# 20190105_ORIGAMI_V1-H.net
KiCad netlist of a schematic drawn in EAGLE
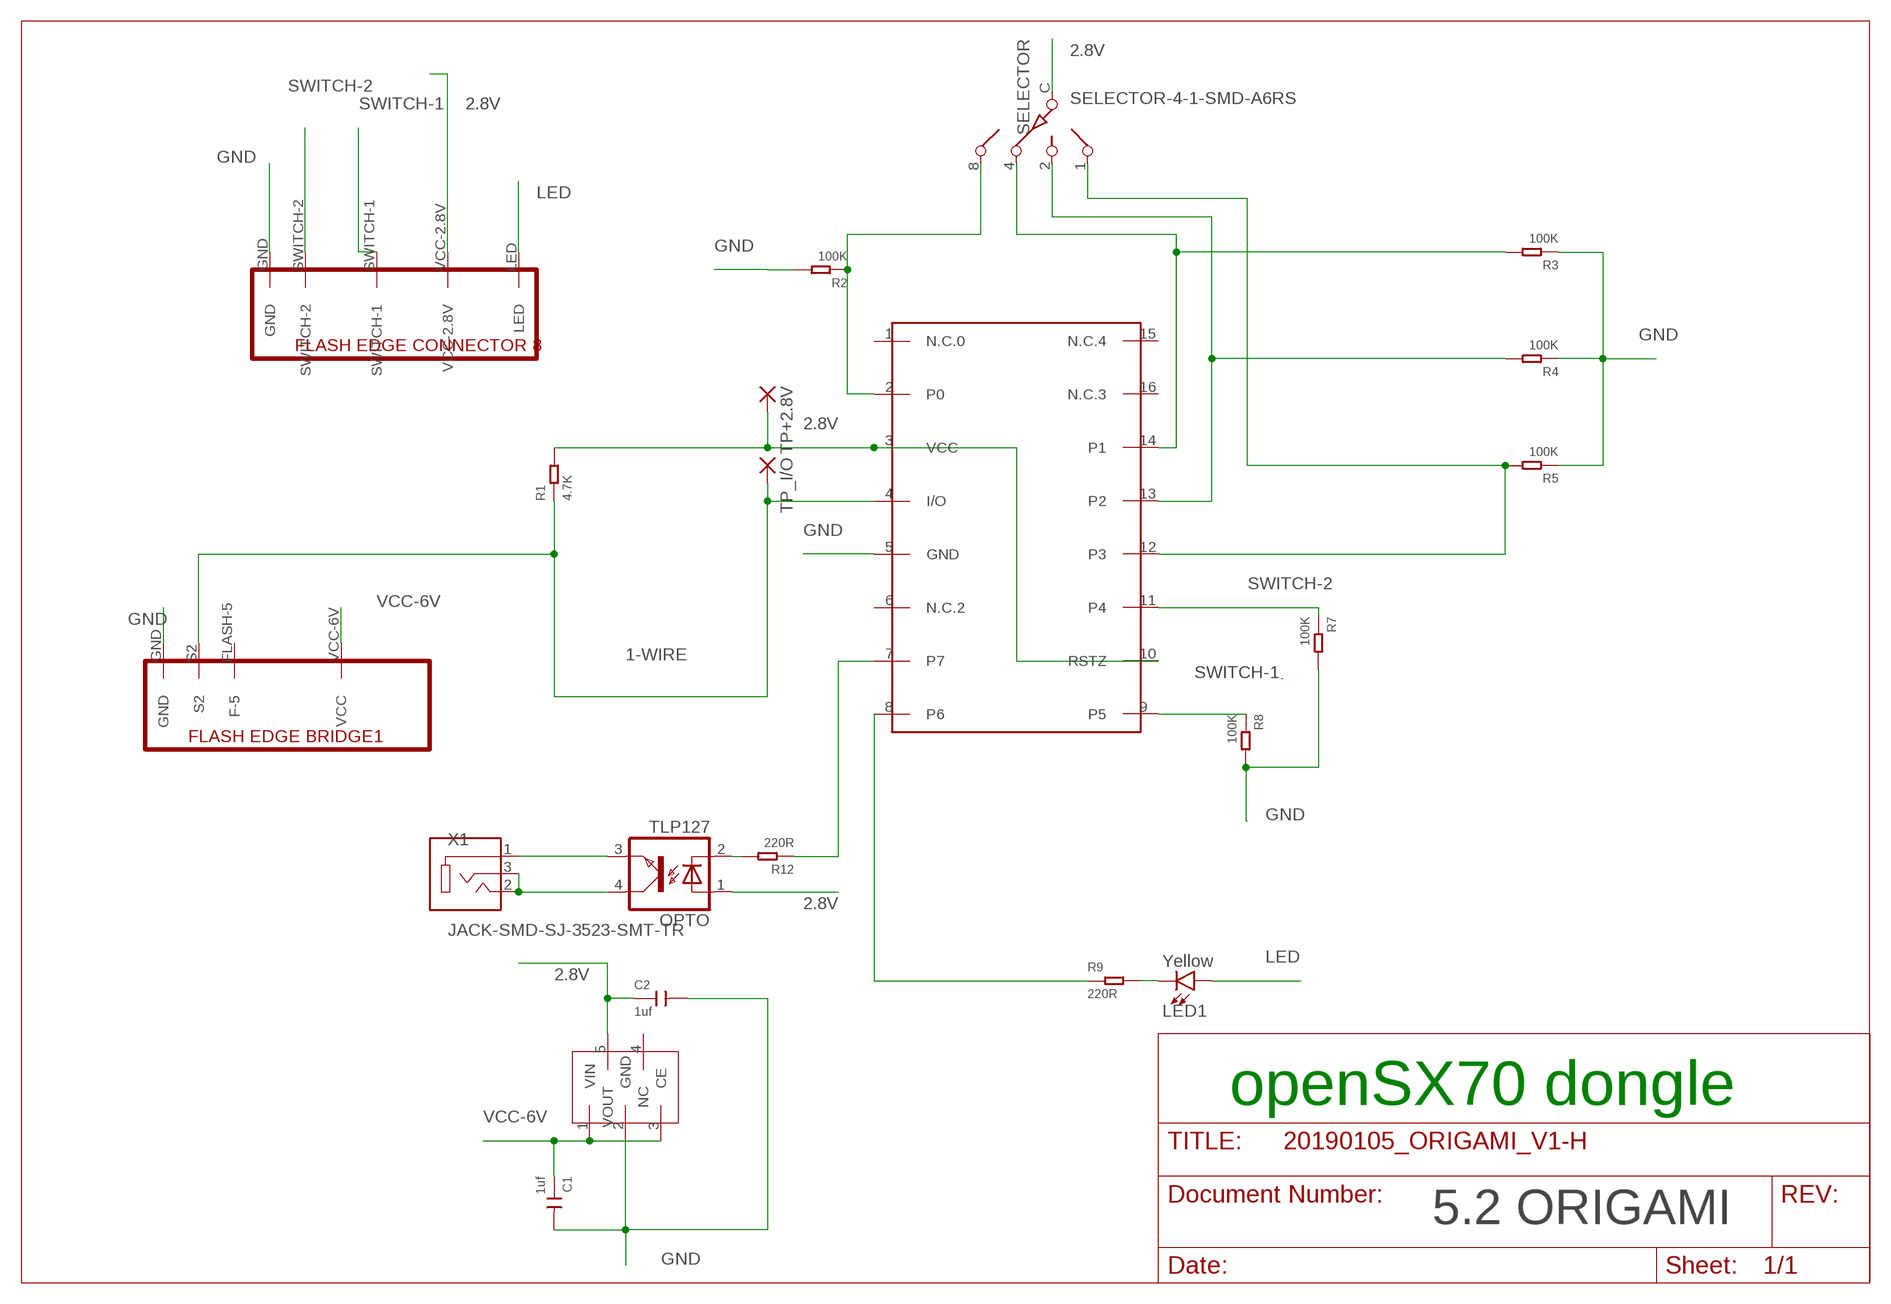
[diagram p0: schematic, sheet 1]

(export (version "E")
  (design (tool "Eeschema 10.0.6"))
  (components
    (comp (ref "C1")
      (value "1uf")
      (footprint "eagle-import:C0603")
      (fields (field (name "MPN") "CC0603KRX7R8BB105"))
      (libsource (lib "eagle-import") (part "CERAMIC-1UF-25V-10%-X7R(0603)"))
    )
    (comp (ref "C2")
      (value "1uf")
      (footprint "eagle-import:C0603")
      (fields (field (name "MPN") "CC0603KRX7R8BB105"))
      (libsource (lib "eagle-import") (part "CERAMIC-1UF-25V-10%-X7R(0603)"))
    )
    (comp (ref "DS2408")
      (value "DS2408")
      (footprint "eagle-import:SO16")
      (libsource (lib "eagle-import") (part "DS2408"))
    )
    (comp (ref "LED1")
      (value "Yellow")
      (footprint "eagle-import:LED-1206")
      (libsource (lib "eagle-import") (part "LED-YELLOWLILYPAD"))
    )
    (comp (ref "OPTO")
      (value "TLP127")
      (footprint "eagle-import:SO-4")
      (libsource (lib "eagle-import") (part "TLP127"))
    )
    (comp (ref "R1")
      (value "4.7K")
      (footprint "eagle-import:R0603")
      (fields (field (name "MPN") "RC0603JR-074K7L"))
      (libsource (lib "eagle-import") (part "SMD-RES-4.7K-5%-1/10W(0603)"))
    )
    (comp (ref "R2")
      (value "100K")
      (footprint "eagle-import:R0603")
      (fields (field (name "MPN") "RC0603FR-07100KL"))
      (libsource (lib "eagle-import") (part "SMD-RES-100K-1%-1/10W(0603)"))
    )
    (comp (ref "R3")
      (value "100K")
      (footprint "eagle-import:R0603")
      (fields (field (name "MPN") "RC0603FR-07100KL"))
      (libsource (lib "eagle-import") (part "SMD-RES-100K-1%-1/10W(0603)"))
    )
    (comp (ref "R4")
      (value "100K")
      (footprint "eagle-import:R0603")
      (fields (field (name "MPN") "RC0603FR-07100KL"))
      (libsource (lib "eagle-import") (part "SMD-RES-100K-1%-1/10W(0603)"))
    )
    (comp (ref "R5")
      (value "100K")
      (footprint "eagle-import:R0603")
      (fields (field (name "MPN") "RC0603FR-07100KL"))
      (libsource (lib "eagle-import") (part "SMD-RES-100K-1%-1/10W(0603)"))
    )
    (comp (ref "R7")
      (value "100K")
      (footprint "eagle-import:R0603")
      (fields (field (name "MPN") "RC0603FR-07100KL"))
      (libsource (lib "eagle-import") (part "SMD-RES-100K-1%-1/10W(0603)"))
    )
    (comp (ref "R8")
      (value "100K")
      (footprint "eagle-import:R0603")
      (fields (field (name "MPN") "RC0603FR-07100KL"))
      (libsource (lib "eagle-import") (part "SMD-RES-100K-1%-1/10W(0603)"))
    )
    (comp (ref "R9")
      (value "220R")
      (footprint "eagle-import:R0603")
      (fields (field (name "MPN") "RC0603JR-07220RL"))
      (libsource (lib "eagle-import") (part "SMD-RES-220R-5%-1/10W(0603)"))
    )
    (comp (ref "R12")
      (value "220R")
      (footprint "eagle-import:R0603")
      (fields (field (name "MPN") "RC0603JR-07220RL"))
      (libsource (lib "eagle-import") (part "SMD-RES-220R-5%-1/10W(0603)"))
    )
    (comp (ref "REG")
      (value "NCP4688")
      (footprint "eagle-import:SOT-23-5")
      (libsource (lib "eagle-import") (part "NCP4688"))
    )
    (comp (ref "SELECTOR")
      (value "SELECTOR-4-1-SMD-A6RS")
      (footprint "eagle-import:A6RS-161RS")
      (libsource (lib "eagle-import") (part "SELECTOR-4-1-SMD-A6RS"))
    )
    (comp (ref "TP+2.8V")
      (value "SMD2")
      (footprint "eagle-import:SMD1,27-2,54")
      (libsource (lib "eagle-import") (part "SMD2"))
    )
    (comp (ref "TP_I/O")
      (value "SMD2")
      (footprint "eagle-import:SMD1,27-2,54")
      (libsource (lib "eagle-import") (part "SMD2"))
    )
    (comp (ref "U$1")
      (value "FLASH-BRIDGE-SW1-SW2-LED")
      (footprint "eagle-import:FLASH-8-BRIDGE-SW1-SW2-LED")
      (libsource (lib "eagle-import") (part "FLASH-BRIDGE-SW1-SW2-LED"))
    )
    (comp (ref "U$2")
      (value "FLASH-BRIDGE1")
      (footprint "eagle-import:FLASH-8-BRIDGE1")
      (libsource (lib "eagle-import") (part "FLASH-BRIDGE1"))
    )
    (comp (ref "X1")
      (value "JACK-SMD-SJ-3523-SMT-TR")
      (footprint "eagle-import:CUI_SJ-3523-SMT-TR")
      (fields (field (name "MF") "CUI Inc.") (field (name "MP") "SJ-3523-SMT-TR"))
      (libsource (lib "eagle-import") (part "JACK-SMD-SJ-3523-SMT-TR"))
    )
  )
  (nets
    (net (code "1") (name "/1-WIRE") (class "Default")
      (node (ref "DS2408") (pin "4") (pinfunction "I/O_4") (pintype "bidirectional"))
      (node (ref "R1") (pin "1") (pinfunction "1_1") (pintype "passive"))
      (node (ref "TP_I/O") (pin "1") (pinfunction "P_1") (pintype "passive"))
      (node (ref "U$2") (pin "S2") (pinfunction "S2_S2") (pintype "bidirectional"))
    )
    (net (code "2") (name "/2.8V") (class "Default")
      (node (ref "C2") (pin "1") (pinfunction "1_1") (pintype "passive"))
      (node (ref "DS2408") (pin "10") (pinfunction "RSTZ_10") (pintype "bidirectional"))
      (node (ref "DS2408") (pin "3") (pinfunction "VCC_3") (pintype "bidirectional"))
      (node (ref "OPTO") (pin "1") (pinfunction "A_1") (pintype "passive"))
      (node (ref "R1") (pin "2") (pinfunction "2_2") (pintype "passive"))
      (node (ref "REG") (pin "5") (pinfunction "VOUT_5") (pintype "bidirectional"))
      (node (ref "SELECTOR") (pin "C") (pinfunction "C_C") (pintype "passive"))
      (node (ref "TP+2.8V") (pin "1") (pinfunction "P_1") (pintype "passive"))
      (node (ref "U$1") (pin "VCC-2.8V") (pinfunction "VCC-2.8V_VCC-2.8V") (pintype "bidirectional"))
    )
    (net (code "3") (name "/GND") (class "Default")
      (node (ref "C1") (pin "2") (pinfunction "2_2") (pintype "passive"))
      (node (ref "C2") (pin "2") (pinfunction "2_2") (pintype "passive"))
      (node (ref "DS2408") (pin "5") (pinfunction "GND_5") (pintype "bidirectional"))
      (node (ref "R2") (pin "2") (pinfunction "2_2") (pintype "passive"))
      (node (ref "R3") (pin "1") (pinfunction "1_1") (pintype "passive"))
      (node (ref "R4") (pin "1") (pinfunction "1_1") (pintype "passive"))
      (node (ref "R5") (pin "1") (pinfunction "1_1") (pintype "passive"))
      (node (ref "R7") (pin "2") (pinfunction "2_2") (pintype "passive"))
      (node (ref "R8") (pin "2") (pinfunction "2_2") (pintype "passive"))
      (node (ref "REG") (pin "2") (pinfunction "GND_2") (pintype "bidirectional"))
      (node (ref "U$1") (pin "GND") (pinfunction "GND_GND") (pintype "bidirectional"))
      (node (ref "U$2") (pin "GND") (pinfunction "GND_GND") (pintype "bidirectional"))
    )
    (net (code "4") (name "/LED") (class "Default")
      (node (ref "LED1") (pin "A") (pinfunction "A_A") (pintype "passive"))
      (node (ref "U$1") (pin "LED") (pinfunction "LED_LED") (pintype "bidirectional"))
    )
    (net (code "5") (name "/SWITCH-1") (class "Default")
      (node (ref "DS2408") (pin "9") (pinfunction "P5_9") (pintype "bidirectional"))
      (node (ref "R8") (pin "1") (pinfunction "1_1") (pintype "passive"))
      (node (ref "U$1") (pin "SWITCH-1") (pinfunction "SWITCH-1_SWITCH-1") (pintype "bidirectional"))
    )
    (net (code "6") (name "/SWITCH-2") (class "Default")
      (node (ref "DS2408") (pin "11") (pinfunction "P4_11") (pintype "bidirectional"))
      (node (ref "R7") (pin "1") (pinfunction "1_1") (pintype "passive"))
      (node (ref "U$1") (pin "SWITCH-2") (pinfunction "SWITCH-2_SWITCH-2") (pintype "bidirectional"))
    )
    (net (code "7") (name "/VCC-6V") (class "Default")
      (node (ref "C1") (pin "1") (pinfunction "1_1") (pintype "passive"))
      (node (ref "REG") (pin "1") (pinfunction "VIN_1") (pintype "bidirectional"))
      (node (ref "REG") (pin "3") (pinfunction "CE_3") (pintype "bidirectional"))
      (node (ref "U$2") (pin "VCC-6V") (pinfunction "VCC_VCC-6V") (pintype "bidirectional"))
    )
    (net (code "8") (name "Net-(DS2408-P0)") (class "Default")
      (node (ref "DS2408") (pin "2") (pinfunction "P0_2") (pintype "bidirectional"))
      (node (ref "R2") (pin "1") (pinfunction "1_1") (pintype "passive"))
      (node (ref "SELECTOR") (pin "8") (pinfunction "8_8") (pintype "passive"))
    )
    (net (code "9") (name "Net-(DS2408-P1)") (class "Default")
      (node (ref "DS2408") (pin "14") (pinfunction "P1_14") (pintype "bidirectional"))
      (node (ref "R3") (pin "2") (pinfunction "2_2") (pintype "passive"))
      (node (ref "SELECTOR") (pin "4") (pinfunction "4_4") (pintype "passive"))
    )
    (net (code "10") (name "Net-(DS2408-P2)") (class "Default")
      (node (ref "DS2408") (pin "13") (pinfunction "P2_13") (pintype "bidirectional"))
      (node (ref "R4") (pin "2") (pinfunction "2_2") (pintype "passive"))
      (node (ref "SELECTOR") (pin "2") (pinfunction "2_2") (pintype "passive"))
    )
    (net (code "11") (name "Net-(DS2408-P3)") (class "Default")
      (node (ref "DS2408") (pin "12") (pinfunction "P3_12") (pintype "bidirectional"))
      (node (ref "R5") (pin "2") (pinfunction "2_2") (pintype "passive"))
      (node (ref "SELECTOR") (pin "1") (pinfunction "1_1") (pintype "passive"))
    )
    (net (code "12") (name "Net-(DS2408-P6)") (class "Default")
      (node (ref "DS2408") (pin "8") (pinfunction "P6_8") (pintype "bidirectional"))
      (node (ref "R9") (pin "1") (pinfunction "1_1") (pintype "passive"))
    )
    (net (code "13") (name "Net-(DS2408-P7)") (class "Default")
      (node (ref "DS2408") (pin "7") (pinfunction "P7_7") (pintype "bidirectional"))
      (node (ref "R12") (pin "1") (pinfunction "1_1") (pintype "passive"))
    )
    (net (code "14") (name "Net-(LED1-PadC)") (class "Default")
      (node (ref "LED1") (pin "C") (pinfunction "C_C") (pintype "passive"))
      (node (ref "R9") (pin "2") (pinfunction "2_2") (pintype "passive"))
    )
    (net (code "15") (name "Net-(OPTO-C)") (class "Default")
      (node (ref "OPTO") (pin "2") (pinfunction "C_2") (pintype "passive"))
      (node (ref "R12") (pin "2") (pinfunction "2_2") (pintype "passive"))
    )
    (net (code "16") (name "Net-(OPTO-COL)") (class "Default")
      (node (ref "OPTO") (pin "4") (pinfunction "COL_4") (pintype "passive"))
      (node (ref "X1") (pin "2") (pinfunction "2_2") (pintype "passive"))
      (node (ref "X1") (pin "3") (pinfunction "3_3") (pintype "passive"))
    )
    (net (code "17") (name "Net-(OPTO-EMIT)") (class "Default")
      (node (ref "OPTO") (pin "3") (pinfunction "EMIT_3") (pintype "passive"))
      (node (ref "X1") (pin "1") (pinfunction "1_1") (pintype "passive"))
    )
    (net (code "18") (name "unconnected-(DS2408-N.C.0-Pad1)") (class "Default")
      (node (ref "DS2408") (pin "1") (pinfunction "N.C.0_1") (pintype "bidirectional"))
    )
    (net (code "19") (name "unconnected-(DS2408-N.C.2-Pad6)") (class "Default")
      (node (ref "DS2408") (pin "6") (pinfunction "N.C.2_6") (pintype "bidirectional"))
    )
    (net (code "20") (name "unconnected-(DS2408-N.C.3-Pad16)") (class "Default")
      (node (ref "DS2408") (pin "16") (pinfunction "N.C.3_16") (pintype "bidirectional"))
    )
    (net (code "21") (name "unconnected-(DS2408-N.C.4-Pad15)") (class "Default")
      (node (ref "DS2408") (pin "15") (pinfunction "N.C.4_15") (pintype "bidirectional"))
    )
    (net (code "22") (name "unconnected-(REG-NC-Pad4)") (class "Default")
      (node (ref "REG") (pin "4") (pinfunction "NC_4") (pintype "bidirectional"))
    )
    (net (code "23") (name "unconnected-(U$2-F-5-PadFLASH-5)") (class "Default")
      (node (ref "U$2") (pin "FLASH-5") (pinfunction "F-5_FLASH-5") (pintype "bidirectional"))
    )
  )
)
